# SDCard.net
KiCad netlist of a schematic drawn in Altium Designer
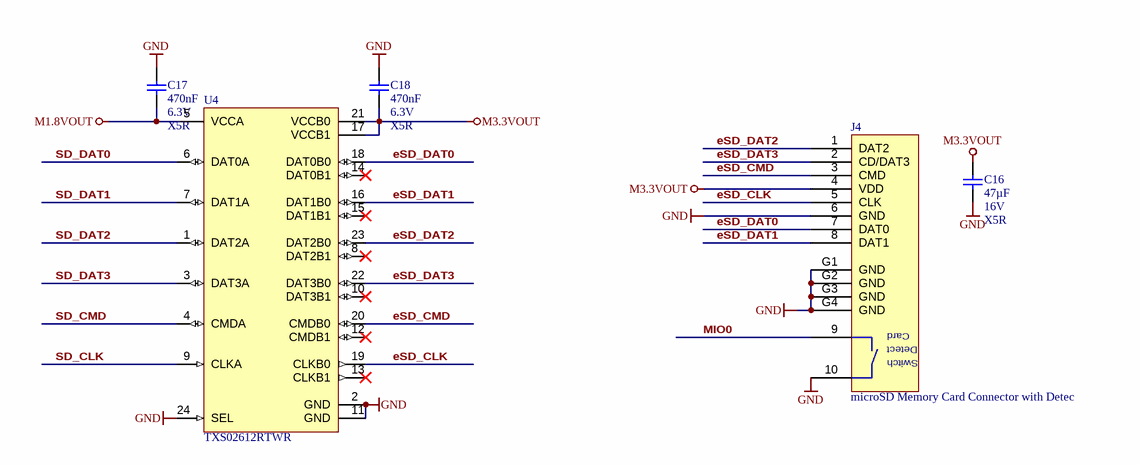
[diagram p0: SDCard.SchDoc]

(export (version "E")
  (design (tool "Eeschema 10.0.6"))
  (components
    (comp (ref "C16")
      (value "47µF")
      (footprint "CAPC3216X180N")
      (description "KON 47µF 16V  X5R SMD 20%")
      (fields
        (field (name "VOLTAGE") "16V")
        (field (name "TECHNOLOGY") "X5R")
        (field (name "TOLERANCE") "20%")
      )
      (libsource (lib "TE") (part "CAP-NP"))
    )
    (comp (ref "C17")
      (value "470nF")
      (footprint "CAPC1005X55N")
      (description "KON 470nF 6,3V X5R SMD")
      (fields (field (name "VOLTAGE") "6.3V") (field (name "TECHNOLOGY") "X5R"))
      (libsource (lib "TE") (part "CAP-NP"))
    )
    (comp (ref "C18")
      (value "470nF")
      (footprint "CAPC1005X55N")
      (description "KON 470nF 6,3V X5R SMD")
      (fields (field (name "VOLTAGE") "6.3V") (field (name "TECHNOLOGY") "X5R"))
      (libsource (lib "TE") (part "CAP-NP"))
    )
    (comp (ref "J4")
      (value "microSD Memory Card Connector with Detec")
      (footprint "104031-0811")
      (description "microSD Memory Card Connector with Detect Switch")
      (libsource (lib "TE") (part "104031-0811"))
    )
    (comp (ref "U4")
      (value "TXS02612RTWR")
      (footprint "QFN50P400X400X80-25N-255")
      (libsource (lib "TE") (part "TXS02612RTWR"))
    )
  )
  (nets
    (net (code "1") (name "/MIO0") (class "Default")
      (node (ref "J4") (pin "9") (pinfunction "CDSW_9") (pintype "passive"))
    )
    (net (code "2") (name "/SD_CLK") (class "Default")
      (node (ref "U4") (pin "9") (pinfunction "CLKA_9") (pintype "input"))
    )
    (net (code "3") (name "/SD_CMD") (class "Default")
      (node (ref "U4") (pin "4") (pinfunction "CMDA_4") (pintype "bidirectional"))
    )
    (net (code "4") (name "/SD_DAT0") (class "Default")
      (node (ref "U4") (pin "6") (pinfunction "DAT0A_6") (pintype "bidirectional"))
    )
    (net (code "5") (name "/SD_DAT1") (class "Default")
      (node (ref "U4") (pin "7") (pinfunction "DAT1A_7") (pintype "bidirectional"))
    )
    (net (code "6") (name "/SD_DAT2") (class "Default")
      (node (ref "U4") (pin "1") (pinfunction "DAT2A_1") (pintype "bidirectional"))
    )
    (net (code "7") (name "/SD_DAT3") (class "Default")
      (node (ref "U4") (pin "3") (pinfunction "DAT3A_3") (pintype "bidirectional"))
    )
    (net (code "8") (name "/eSD_CLK") (class "Default")
      (node (ref "J4") (pin "5") (pinfunction "CLK_5") (pintype "passive"))
      (node (ref "U4") (pin "19") (pinfunction "CLKB0_19") (pintype "output"))
    )
    (net (code "9") (name "/eSD_CMD") (class "Default")
      (node (ref "J4") (pin "3") (pinfunction "CMD_3") (pintype "passive"))
      (node (ref "U4") (pin "20") (pinfunction "CMDB0_20") (pintype "bidirectional"))
    )
    (net (code "10") (name "/eSD_DAT0") (class "Default")
      (node (ref "J4") (pin "7") (pinfunction "DAT0_7") (pintype "passive"))
      (node (ref "U4") (pin "18") (pinfunction "DAT0B0_18") (pintype "bidirectional"))
    )
    (net (code "11") (name "/eSD_DAT1") (class "Default")
      (node (ref "J4") (pin "8") (pinfunction "DAT1_8") (pintype "passive"))
      (node (ref "U4") (pin "16") (pinfunction "DAT1B0_16") (pintype "bidirectional"))
    )
    (net (code "12") (name "/eSD_DAT2") (class "Default")
      (node (ref "J4") (pin "1") (pinfunction "DAT2_1") (pintype "passive"))
      (node (ref "U4") (pin "23") (pinfunction "DAT2B0_23") (pintype "bidirectional"))
    )
    (net (code "13") (name "/eSD_DAT3") (class "Default")
      (node (ref "J4") (pin "2") (pinfunction "CD/DAT3_2") (pintype "passive"))
      (node (ref "U4") (pin "22") (pinfunction "DAT3B0_22") (pintype "bidirectional"))
    )
    (net (code "14") (name "GND") (class "Default")
      (node (ref "C16") (pin "1") (pinfunction "1_1") (pintype "passive"))
      (node (ref "C17") (pin "2") (pinfunction "2_2") (pintype "passive"))
      (node (ref "C18") (pin "2") (pinfunction "2_2") (pintype "passive"))
      (node (ref "J4") (pin "10") (pinfunction "CDSW_10") (pintype "passive"))
      (node (ref "J4") (pin "6") (pinfunction "GND_6") (pintype "passive"))
      (node (ref "J4") (pin "G1") (pinfunction "GND_G1") (pintype "passive"))
      (node (ref "J4") (pin "G2") (pinfunction "GND_G2") (pintype "passive"))
      (node (ref "J4") (pin "G3") (pinfunction "GND_G3") (pintype "passive"))
      (node (ref "J4") (pin "G4") (pinfunction "GND_G4") (pintype "passive"))
      (node (ref "U4") (pin "11") (pinfunction "GND_11") (pintype "power_in"))
      (node (ref "U4") (pin "2") (pinfunction "GND_2") (pintype "power_in"))
      (node (ref "U4") (pin "24") (pinfunction "SEL_24") (pintype "input"))
    )
    (net (code "15") (name "M1.8VOUT") (class "Default")
      (node (ref "C17") (pin "1") (pinfunction "1_1") (pintype "passive"))
      (node (ref "U4") (pin "5") (pinfunction "VCCA_5") (pintype "power_in"))
    )
    (net (code "16") (name "M3.3VOUT") (class "Default")
      (node (ref "C16") (pin "2") (pinfunction "2_2") (pintype "passive"))
      (node (ref "C18") (pin "1") (pinfunction "1_1") (pintype "passive"))
      (node (ref "J4") (pin "4") (pinfunction "VDD_4") (pintype "passive"))
      (node (ref "U4") (pin "17") (pinfunction "VCCB1_17") (pintype "power_in"))
      (node (ref "U4") (pin "21") (pinfunction "VCCB0_21") (pintype "power_in"))
    )
    (net (code "17") (name "unconnected-(U4-CLKB1-Pad13)") (class "Default")
      (node (ref "U4") (pin "13") (pinfunction "CLKB1_13") (pintype "output+no_connect"))
    )
    (net (code "18") (name "unconnected-(U4-CMDB1-Pad12)") (class "Default")
      (node (ref "U4") (pin "12") (pinfunction "CMDB1_12") (pintype "bidirectional+no_connect"))
    )
    (net (code "19") (name "unconnected-(U4-DAT0B1-Pad14)") (class "Default")
      (node (ref "U4") (pin "14") (pinfunction "DAT0B1_14") (pintype "bidirectional+no_connect"))
    )
    (net (code "20") (name "unconnected-(U4-DAT1B1-Pad15)") (class "Default")
      (node (ref "U4") (pin "15") (pinfunction "DAT1B1_15") (pintype "bidirectional+no_connect"))
    )
    (net (code "21") (name "unconnected-(U4-DAT2B1-Pad8)") (class "Default")
      (node (ref "U4") (pin "8") (pinfunction "DAT2B1_8") (pintype "bidirectional+no_connect"))
    )
    (net (code "22") (name "unconnected-(U4-DAT3B1-Pad10)") (class "Default")
      (node (ref "U4") (pin "10") (pinfunction "DAT3B1_10") (pintype "bidirectional+no_connect"))
    )
  )
)
